# Sonar_Power_Schematic_LT1962_5_33.net
KiCad netlist of a schematic drawn in EAGLE
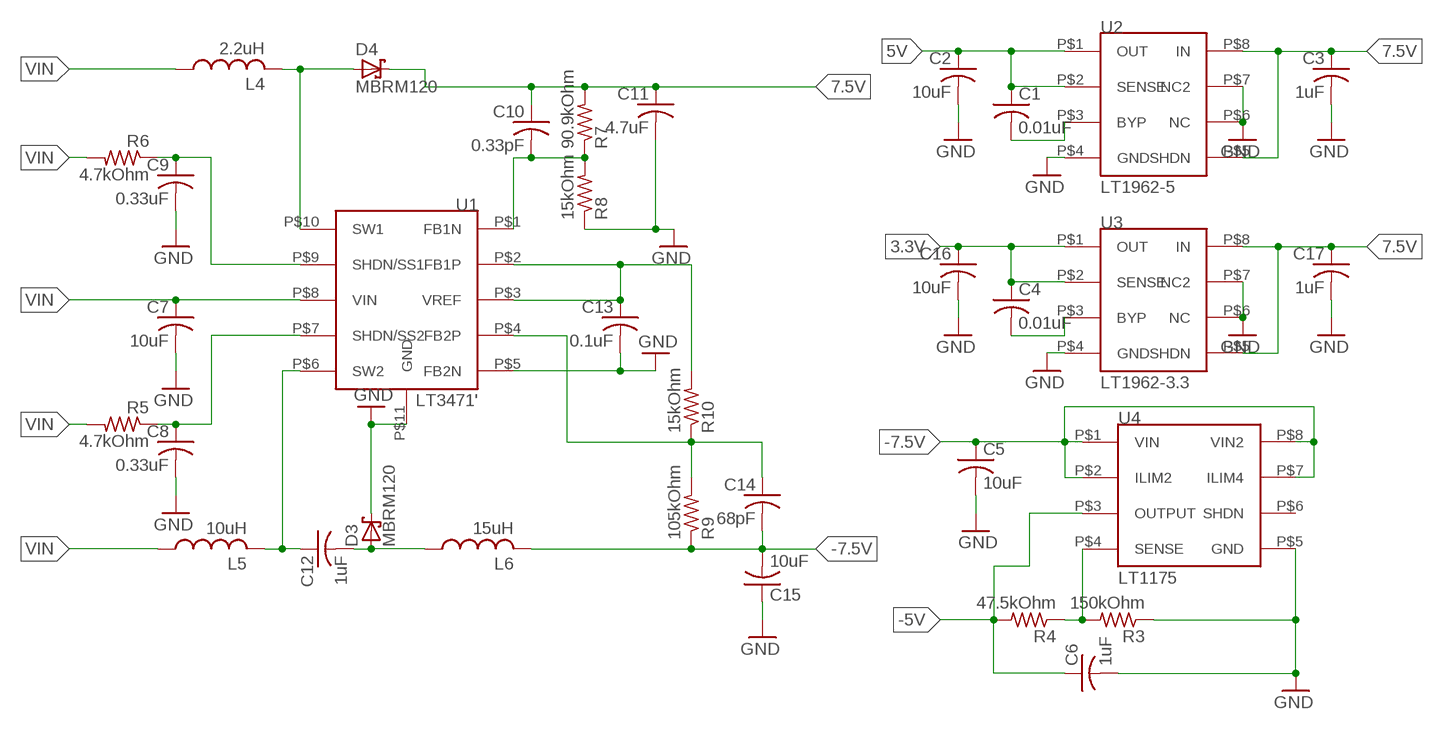
[diagram p0: schematic, sheet 1]

(export (version "E")
  (design (tool "Eeschema 10.0.6"))
  (components
    (comp (ref "C1")
      (value "0.01uF")
      (footprint "eagle-import:C0603")
      (libsource (lib "eagle-import") (part "C-USC0603"))
    )
    (comp (ref "C2")
      (value "10uF")
      (footprint "eagle-import:C0603")
      (libsource (lib "eagle-import") (part "C-USC0603"))
    )
    (comp (ref "C3")
      (value "1uF")
      (footprint "eagle-import:C0603")
      (libsource (lib "eagle-import") (part "C-USC0603"))
    )
    (comp (ref "C4")
      (value "0.01uF")
      (footprint "eagle-import:C0603")
      (libsource (lib "eagle-import") (part "C-USC0603"))
    )
    (comp (ref "C5")
      (value "10uF")
      (footprint "eagle-import:C0603")
      (libsource (lib "eagle-import") (part "C-USC0603"))
    )
    (comp (ref "C6")
      (value "1uF")
      (footprint "eagle-import:C0603")
      (libsource (lib "eagle-import") (part "C-USC0603"))
    )
    (comp (ref "C7")
      (value "10uF")
      (footprint "eagle-import:C0603")
      (libsource (lib "eagle-import") (part "C-USC0603"))
    )
    (comp (ref "C8")
      (value "0.33uF")
      (footprint "eagle-import:C0603")
      (libsource (lib "eagle-import") (part "C-USC0603"))
    )
    (comp (ref "C9")
      (value "0.33uF")
      (footprint "eagle-import:C0603")
      (libsource (lib "eagle-import") (part "C-USC0603"))
    )
    (comp (ref "C10")
      (value "0.33pF")
      (footprint "eagle-import:C0603")
      (libsource (lib "eagle-import") (part "C-USC0603"))
    )
    (comp (ref "C11")
      (value "4.7uF")
      (footprint "eagle-import:C0603")
      (libsource (lib "eagle-import") (part "C-USC0603"))
    )
    (comp (ref "C12")
      (value "1uF")
      (footprint "eagle-import:C0603")
      (libsource (lib "eagle-import") (part "C-USC0603"))
    )
    (comp (ref "C13")
      (value "0.1uF")
      (footprint "eagle-import:C0603")
      (libsource (lib "eagle-import") (part "C-USC0603"))
    )
    (comp (ref "C14")
      (value "68pF")
      (footprint "eagle-import:C0603")
      (libsource (lib "eagle-import") (part "C-USC0603"))
    )
    (comp (ref "C15")
      (value "10uF")
      (footprint "eagle-import:C0603")
      (libsource (lib "eagle-import") (part "C-USC0603"))
    )
    (comp (ref "C16")
      (value "10uF")
      (footprint "eagle-import:C0603")
      (libsource (lib "eagle-import") (part "C-USC0603"))
    )
    (comp (ref "C17")
      (value "1uF")
      (footprint "eagle-import:C0603")
      (libsource (lib "eagle-import") (part "C-USC0603"))
    )
    (comp (ref "D3")
      (value "MBRM120")
      (footprint "eagle-import:DO-216AA")
      (libsource (lib "eagle-import") (part "MBRM120"))
    )
    (comp (ref "D4")
      (value "MBRM120")
      (footprint "eagle-import:DO-216AA")
      (libsource (lib "eagle-import") (part "MBRM120"))
    )
    (comp (ref "L4")
      (value "2.2uH")
      (footprint "eagle-import:NS4.9X4.9")
      (libsource (lib "eagle-import") (part "LQH5BPN2R2N38L"))
    )
    (comp (ref "L5")
      (value "10uH")
      (footprint "eagle-import:NS5X5")
      (libsource (lib "eagle-import") (part "VLS5045EX-100M2"))
    )
    (comp (ref "L6")
      (value "15uH")
      (footprint "eagle-import:NS5X5")
      (libsource (lib "eagle-import") (part "VLS5045EX-150M-CA1"))
    )
    (comp (ref "R3")
      (value "150kOhm")
      (footprint "eagle-import:R0603")
      (libsource (lib "eagle-import") (part "R-US_R0603"))
    )
    (comp (ref "R4")
      (value "47.5kOhm")
      (footprint "eagle-import:R0603")
      (libsource (lib "eagle-import") (part "R-US_R0603"))
    )
    (comp (ref "R5")
      (value "4.7kOhm")
      (footprint "eagle-import:R0603")
      (libsource (lib "eagle-import") (part "R-US_R0603"))
    )
    (comp (ref "R6")
      (value "4.7kOhm")
      (footprint "eagle-import:R0603")
      (libsource (lib "eagle-import") (part "R-US_R0603"))
    )
    (comp (ref "R7")
      (value "90.9kOhm")
      (footprint "eagle-import:R0603")
      (libsource (lib "eagle-import") (part "R-US_R0603"))
    )
    (comp (ref "R8")
      (value "15kOhm")
      (footprint "eagle-import:R0603")
      (libsource (lib "eagle-import") (part "R-US_R0603"))
    )
    (comp (ref "R9")
      (value "105kOhm")
      (footprint "eagle-import:R0603")
      (libsource (lib "eagle-import") (part "R-US_R0603"))
    )
    (comp (ref "R10")
      (value "15kOhm")
      (footprint "eagle-import:R0603")
      (libsource (lib "eagle-import") (part "R-US_R0603"))
    )
    (comp (ref "U1")
      (value "LT3471'")
      (footprint "eagle-import:10-WFDFN")
      (libsource (lib "eagle-import") (part "LT3471'"))
    )
    (comp (ref "U2")
      (value "LT1962-5")
      (footprint "eagle-import:8-MSOP")
      (libsource (lib "eagle-import") (part "LT1962-5"))
    )
    (comp (ref "U3")
      (value "LT1962-3.3")
      (footprint "eagle-import:8-MSOP")
      (libsource (lib "eagle-import") (part "LT1962-3.3"))
    )
    (comp (ref "U4")
      (value "LT1175")
      (footprint "eagle-import:8-SOIC")
      (libsource (lib "eagle-import") (part "LT1175"))
    )
  )
  (nets
    (net (code "1") (name "-5V") (class "Default")
      (node (ref "C6") (pin "1") (pinfunction "1_1") (pintype "passive"))
      (node (ref "R4") (pin "2") (pinfunction "2_2") (pintype "passive"))
      (node (ref "U4") (pin "P$3") (pinfunction "OUTPUT_P$3") (pintype "bidirectional"))
    )
    (net (code "2") (name "-7.5V") (class "Default")
      (node (ref "C14") (pin "2") (pinfunction "2_2") (pintype "passive"))
      (node (ref "C15") (pin "2") (pinfunction "2_2") (pintype "passive"))
      (node (ref "C5") (pin "1") (pinfunction "1_1") (pintype "passive"))
      (node (ref "L6") (pin "P$2") (pinfunction "2_P$2") (pintype "passive"))
      (node (ref "R9") (pin "1") (pinfunction "1_1") (pintype "passive"))
      (node (ref "U4") (pin "P$1") (pinfunction "VIN_P$1") (pintype "power_in"))
      (node (ref "U4") (pin "P$2") (pinfunction "ILIM2_P$2") (pintype "bidirectional"))
      (node (ref "U4") (pin "P$7") (pinfunction "ILIM4_P$7") (pintype "bidirectional"))
      (node (ref "U4") (pin "P$8") (pinfunction "VIN2_P$8") (pintype "power_in"))
    )
    (net (code "3") (name "3.3V") (class "Default")
      (node (ref "C16") (pin "1") (pinfunction "1_1") (pintype "passive"))
      (node (ref "C4") (pin "1") (pinfunction "1_1") (pintype "passive"))
      (node (ref "U3") (pin "P$1") (pinfunction "OUT_P$1") (pintype "bidirectional"))
      (node (ref "U3") (pin "P$2") (pinfunction "SENSE_P$2") (pintype "bidirectional"))
    )
    (net (code "4") (name "5V") (class "Default")
      (node (ref "C1") (pin "1") (pinfunction "1_1") (pintype "passive"))
      (node (ref "C2") (pin "1") (pinfunction "1_1") (pintype "passive"))
      (node (ref "U2") (pin "P$1") (pinfunction "OUT_P$1") (pintype "bidirectional"))
      (node (ref "U2") (pin "P$2") (pinfunction "SENSE_P$2") (pintype "bidirectional"))
    )
    (net (code "5") (name "7.5V") (class "Default")
      (node (ref "C10") (pin "1") (pinfunction "1_1") (pintype "passive"))
      (node (ref "C11") (pin "1") (pinfunction "1_1") (pintype "passive"))
      (node (ref "C17") (pin "1") (pinfunction "1_1") (pintype "passive"))
      (node (ref "C3") (pin "1") (pinfunction "1_1") (pintype "passive"))
      (node (ref "D4") (pin "P$1") (pinfunction "C_P$1") (pintype "passive"))
      (node (ref "R7") (pin "2") (pinfunction "2_2") (pintype "passive"))
      (node (ref "U2") (pin "P$5") (pinfunction "SHDN_P$5") (pintype "bidirectional"))
      (node (ref "U2") (pin "P$8") (pinfunction "IN_P$8") (pintype "bidirectional"))
      (node (ref "U3") (pin "P$5") (pinfunction "SHDN_P$5") (pintype "bidirectional"))
      (node (ref "U3") (pin "P$8") (pinfunction "IN_P$8") (pintype "bidirectional"))
    )
    (net (code "6") (name "GND") (class "Default")
      (node (ref "C11") (pin "2") (pinfunction "2_2") (pintype "passive"))
      (node (ref "C13") (pin "2") (pinfunction "2_2") (pintype "passive"))
      (node (ref "C15") (pin "1") (pinfunction "1_1") (pintype "passive"))
      (node (ref "C16") (pin "2") (pinfunction "2_2") (pintype "passive"))
      (node (ref "C17") (pin "2") (pinfunction "2_2") (pintype "passive"))
      (node (ref "C2") (pin "2") (pinfunction "2_2") (pintype "passive"))
      (node (ref "C3") (pin "2") (pinfunction "2_2") (pintype "passive"))
      (node (ref "C5") (pin "2") (pinfunction "2_2") (pintype "passive"))
      (node (ref "C6") (pin "2") (pinfunction "2_2") (pintype "passive"))
      (node (ref "C7") (pin "2") (pinfunction "2_2") (pintype "passive"))
      (node (ref "C8") (pin "2") (pinfunction "2_2") (pintype "passive"))
      (node (ref "C9") (pin "2") (pinfunction "2_2") (pintype "passive"))
      (node (ref "D3") (pin "P$1") (pinfunction "C_P$1") (pintype "passive"))
      (node (ref "R3") (pin "1") (pinfunction "1_1") (pintype "passive"))
      (node (ref "R8") (pin "1") (pinfunction "1_1") (pintype "passive"))
      (node (ref "U1") (pin "P$11") (pinfunction "GND_P$11") (pintype "power_in"))
      (node (ref "U1") (pin "P$5") (pinfunction "FB2N_P$5") (pintype "bidirectional"))
      (node (ref "U2") (pin "P$4") (pinfunction "GND_P$4") (pintype "bidirectional"))
      (node (ref "U2") (pin "P$6") (pinfunction "NC_P$6") (pintype "bidirectional"))
      (node (ref "U2") (pin "P$7") (pinfunction "NC2_P$7") (pintype "bidirectional"))
      (node (ref "U3") (pin "P$4") (pinfunction "GND_P$4") (pintype "bidirectional"))
      (node (ref "U3") (pin "P$6") (pinfunction "NC_P$6") (pintype "bidirectional"))
      (node (ref "U3") (pin "P$7") (pinfunction "NC2_P$7") (pintype "bidirectional"))
      (node (ref "U4") (pin "P$5") (pinfunction "GND_P$5") (pintype "power_in"))
    )
    (net (code "7") (name "Net-(D3-A)") (class "Default")
      (node (ref "C12") (pin "2") (pinfunction "2_2") (pintype "passive"))
      (node (ref "D3") (pin "P$2") (pinfunction "A_P$2") (pintype "passive"))
      (node (ref "L6") (pin "P$1") (pinfunction "1_P$1") (pintype "passive"))
    )
    (net (code "8") (name "Net-(D4-A)") (class "Default")
      (node (ref "D4") (pin "P$2") (pinfunction "A_P$2") (pintype "passive"))
      (node (ref "L4") (pin "P$2") (pinfunction "2_P$2") (pintype "passive"))
      (node (ref "U1") (pin "P$10") (pinfunction "SW1_P$10") (pintype "bidirectional"))
    )
    (net (code "9") (name "Net-(L5-2)") (class "Default")
      (node (ref "C12") (pin "1") (pinfunction "1_1") (pintype "passive"))
      (node (ref "L5") (pin "P$2") (pinfunction "2_P$2") (pintype "passive"))
      (node (ref "U1") (pin "P$6") (pinfunction "SW2_P$6") (pintype "bidirectional"))
    )
    (net (code "10") (name "Net-(U1-FB1N)") (class "Default")
      (node (ref "C10") (pin "2") (pinfunction "2_2") (pintype "passive"))
      (node (ref "R7") (pin "1") (pinfunction "1_1") (pintype "passive"))
      (node (ref "R8") (pin "2") (pinfunction "2_2") (pintype "passive"))
      (node (ref "U1") (pin "P$1") (pinfunction "FB1N_P$1") (pintype "bidirectional"))
    )
    (net (code "11") (name "Net-(U1-FB1P)") (class "Default")
      (node (ref "C13") (pin "1") (pinfunction "1_1") (pintype "passive"))
      (node (ref "R10") (pin "2") (pinfunction "2_2") (pintype "passive"))
      (node (ref "U1") (pin "P$2") (pinfunction "FB1P_P$2") (pintype "bidirectional"))
      (node (ref "U1") (pin "P$3") (pinfunction "VREF_P$3") (pintype "power_in"))
    )
    (net (code "12") (name "Net-(U1-FB2P)") (class "Default")
      (node (ref "C14") (pin "1") (pinfunction "1_1") (pintype "passive"))
      (node (ref "R10") (pin "1") (pinfunction "1_1") (pintype "passive"))
      (node (ref "R9") (pin "2") (pinfunction "2_2") (pintype "passive"))
      (node (ref "U1") (pin "P$4") (pinfunction "FB2P_P$4") (pintype "bidirectional"))
    )
    (net (code "13") (name "Net-(U1-SHDN{slash}SS1)") (class "Default")
      (node (ref "C9") (pin "1") (pinfunction "1_1") (pintype "passive"))
      (node (ref "R6") (pin "1") (pinfunction "1_1") (pintype "passive"))
      (node (ref "U1") (pin "P$9") (pinfunction "SHDN/SS1_P$9") (pintype "bidirectional"))
    )
    (net (code "14") (name "Net-(U1-SHDN{slash}SS2)") (class "Default")
      (node (ref "C8") (pin "1") (pinfunction "1_1") (pintype "passive"))
      (node (ref "R5") (pin "1") (pinfunction "1_1") (pintype "passive"))
      (node (ref "U1") (pin "P$7") (pinfunction "SHDN/SS2_P$7") (pintype "bidirectional"))
    )
    (net (code "15") (name "Net-(U2-BYP)") (class "Default")
      (node (ref "C1") (pin "2") (pinfunction "2_2") (pintype "passive"))
      (node (ref "U2") (pin "P$3") (pinfunction "BYP_P$3") (pintype "bidirectional"))
    )
    (net (code "16") (name "Net-(U3-BYP)") (class "Default")
      (node (ref "C4") (pin "2") (pinfunction "2_2") (pintype "passive"))
      (node (ref "U3") (pin "P$3") (pinfunction "BYP_P$3") (pintype "bidirectional"))
    )
    (net (code "17") (name "Net-(U4-SENSE)") (class "Default")
      (node (ref "R3") (pin "2") (pinfunction "2_2") (pintype "passive"))
      (node (ref "R4") (pin "1") (pinfunction "1_1") (pintype "passive"))
      (node (ref "U4") (pin "P$4") (pinfunction "SENSE_P$4") (pintype "bidirectional"))
    )
    (net (code "18") (name "VIN") (class "Default")
      (node (ref "C7") (pin "1") (pinfunction "1_1") (pintype "passive"))
      (node (ref "L4") (pin "P$1") (pinfunction "1_P$1") (pintype "passive"))
      (node (ref "L5") (pin "P$1") (pinfunction "1_P$1") (pintype "passive"))
      (node (ref "R5") (pin "2") (pinfunction "2_2") (pintype "passive"))
      (node (ref "R6") (pin "2") (pinfunction "2_2") (pintype "passive"))
      (node (ref "U1") (pin "P$8") (pinfunction "VIN_P$8") (pintype "power_in"))
    )
    (net (code "19") (name "unconnected-(U4-SHDN-PadP$6)") (class "Default")
      (node (ref "U4") (pin "P$6") (pinfunction "SHDN_P$6") (pintype "bidirectional"))
    )
  )
)
